# zxld381-boost-driver-24mm-mk-1.net
KiCad netlist of a schematic drawn in EAGLE
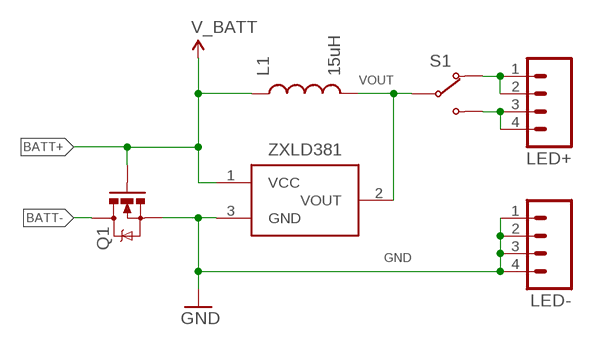
[diagram p0: schematic, sheet 1]

(export (version "E")
  (design (tool "Eeschema 10.0.6"))
  (components
    (comp (ref "L1")
      (value "15uH")
      (footprint "eagle-import:0805")
      (libsource (lib "eagle-import") (part "INDUCTOR0805"))
    )
    (comp (ref "LED+")
      (value "M04PTH")
      (footprint "eagle-import:1X04-PTH-VERT")
      (libsource (lib "eagle-import") (part "M04PTH"))
    )
    (comp (ref "LED-")
      (value "M04PTH")
      (footprint "eagle-import:1X04-PTH-VERT")
      (libsource (lib "eagle-import") (part "M04PTH"))
    )
    (comp (ref "Q1")
      (value "MOSFET-NCHANNELIRLML2502")
      (footprint "eagle-import:SOT23")
      (libsource (lib "eagle-import") (part "MOSFET-NCHANNELIRLML2502"))
    )
    (comp (ref "S1")
      (value "SWITCH-SPDTPTH-RA-2MM")
      (footprint "eagle-import:SPDT-RA-2MM")
      (libsource (lib "eagle-import") (part "SWITCH-SPDTPTH-RA-2MM"))
    )
    (comp (ref "ZXLD381")
      (value "ZXLD381")
      (footprint "eagle-import:SOT23-3")
      (libsource (lib "eagle-import") (part "ZXLD381"))
    )
  )
  (nets
    (net (code "1") (name "/VOUT") (class "Default")
      (node (ref "L1") (pin "2") (pinfunction "2_2") (pintype "passive"))
      (node (ref "S1") (pin "2") (pinfunction "COM_2") (pintype "passive"))
      (node (ref "ZXLD381") (pin "2") (pinfunction "VOUT_2") (pintype "bidirectional"))
    )
    (net (code "2") (name "BATT+") (class "Default")
      (node (ref "L1") (pin "1") (pinfunction "1_1") (pintype "passive"))
      (node (ref "Q1") (pin "1") (pinfunction "G_1") (pintype "passive"))
      (node (ref "ZXLD381") (pin "1") (pinfunction "VCC_1") (pintype "bidirectional"))
    )
    (net (code "3") (name "BATT-") (class "Default")
      (node (ref "Q1") (pin "3") (pinfunction "D_3") (pintype "passive"))
    )
    (net (code "4") (name "GND") (class "Default")
      (node (ref "LED-") (pin "1") (pinfunction "1_1") (pintype "passive"))
      (node (ref "LED-") (pin "2") (pinfunction "2_2") (pintype "passive"))
      (node (ref "LED-") (pin "3") (pinfunction "3_3") (pintype "passive"))
      (node (ref "LED-") (pin "4") (pinfunction "4_4") (pintype "passive"))
      (node (ref "Q1") (pin "2") (pinfunction "S_2") (pintype "passive"))
      (node (ref "ZXLD381") (pin "3") (pinfunction "GND_3") (pintype "bidirectional"))
    )
    (net (code "5") (name "Net-(S1-NC)") (class "Default")
      (node (ref "LED+") (pin "1") (pinfunction "1_1") (pintype "passive"))
      (node (ref "LED+") (pin "2") (pinfunction "2_2") (pintype "passive"))
      (node (ref "S1") (pin "1") (pinfunction "NC_1") (pintype "passive"))
    )
    (net (code "6") (name "Net-(S1-NO)") (class "Default")
      (node (ref "LED+") (pin "3") (pinfunction "3_3") (pintype "passive"))
      (node (ref "LED+") (pin "4") (pinfunction "4_4") (pintype "passive"))
      (node (ref "S1") (pin "3") (pinfunction "NO_3") (pintype "passive"))
    )
  )
)
